# Power.net
KiCad netlist of a schematic drawn in Altium Designer
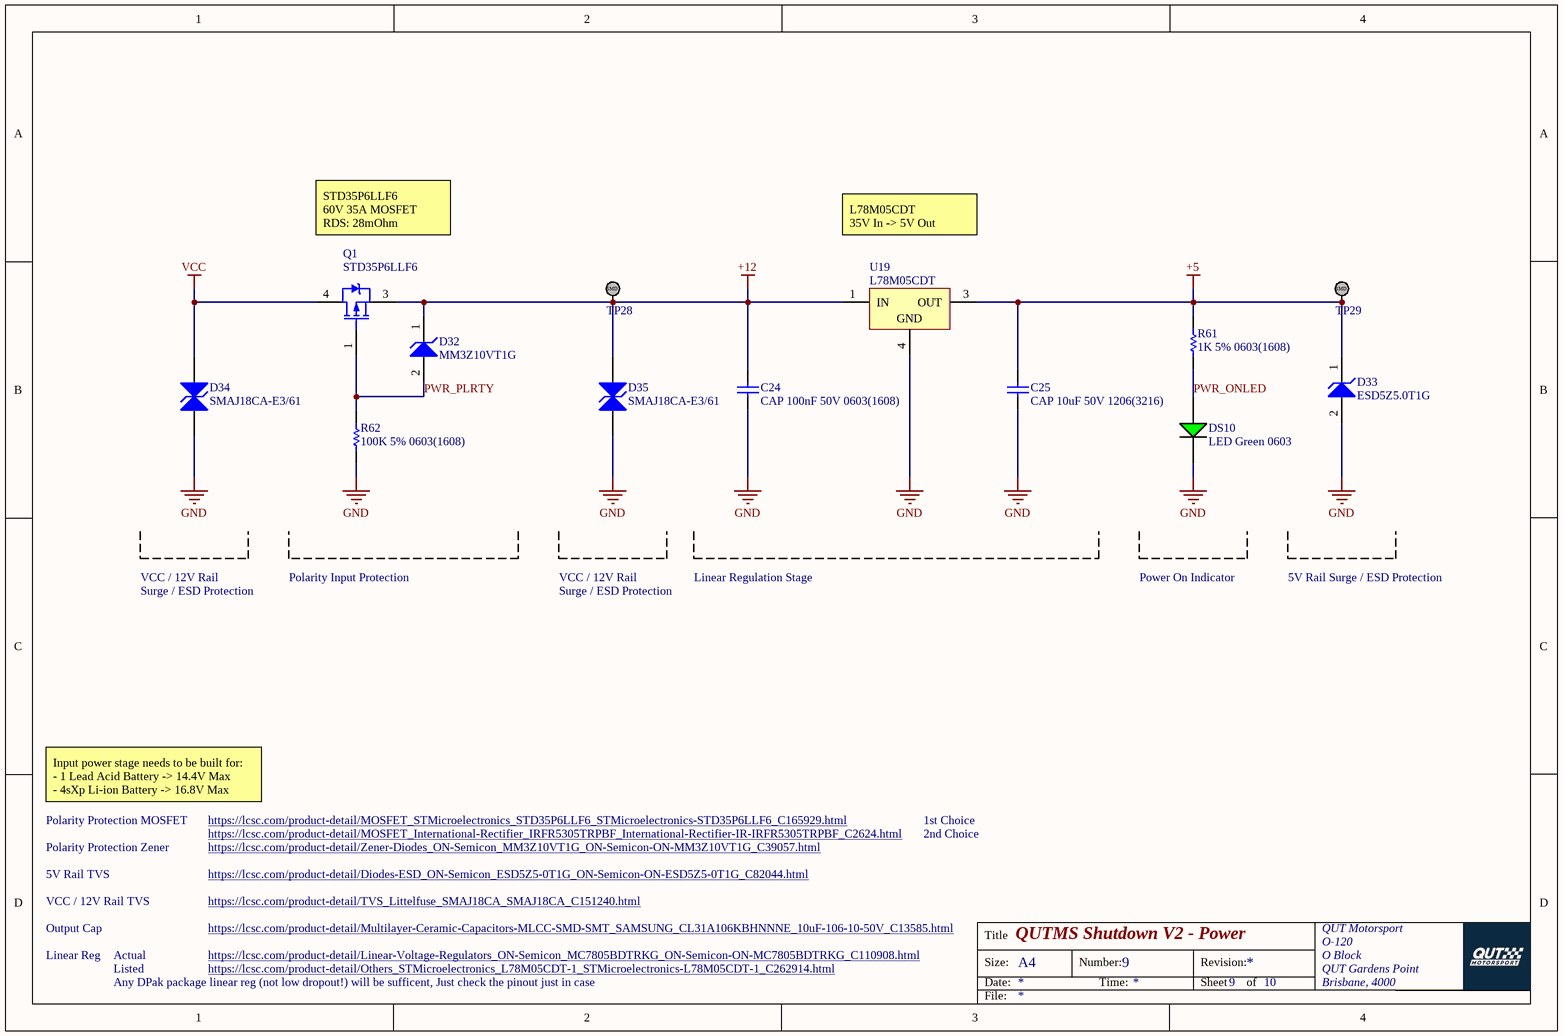
[diagram p0: Power.SchDoc]

(export (version "E")
  (design (tool "Eeschema 10.0.6"))
  (components
    (comp (ref "C24")
      (value "CAP 100nF 50V 0603(1608)")
      (footprint "CAPC0603(1608)100_N")
      (description "CAP 100nF 50V ±5% 0603 (1608 Metric) Thickness 1mm SMD")
      (fields (field (name "TOLERANCE") "Â±5%"))
      (libsource (lib "Altium Content Vault") (part "CAP"))
    )
    (comp (ref "C25")
      (value "CAP 10uF 50V 1206(3216)")
      (footprint "CAPC1206(3216)190_N")
      (description "CAP 10uF 50V ±10% 1206 (3216 Metric) Thickness 1.9mm SMD")
      (fields (field (name "TOLERANCE") "Â±10%"))
      (libsource (lib "Altium Content Vault") (part "CAP"))
    )
    (comp (ref "D32")
      (value "MM3Z10VT1G")
      (footprint "ONSC-SOD-323-2-477-02_V")
      (description "Zener Voltage Regulator, 300 mW, 2-Pin SOD-323, Pb-Free, Tape and Reel")
      (fields (field (name "MANUFACTURER") "On Semiconductor"))
      (libsource (lib "Altium Content Vault") (part "ONSC-K1A2-2"))
    )
    (comp (ref "D33")
      (value "ESD5Z5.0T1G")
      (footprint "ONSC-SOD-523-2-502-01_V")
      (fields (field (name "MANUFACTURER") "On Semiconductor"))
      (libsource (lib "Altium Content Vault") (part "ONSC-K1A2-2"))
    )
    (comp (ref "D34")
      (value "SMAJ18CA-E3/61")
      (footprint "VISH-DO-214AC-2_N")
      (fields (field (name "MANUFACTURER") "Vishay Semiconductor"))
      (libsource (lib "Altium Content Vault") (part "VISH-A1A2-2"))
    )
    (comp (ref "D35")
      (value "SMAJ18CA-E3/61")
      (footprint "VISH-DO-214AC-2_N")
      (fields (field (name "MANUFACTURER") "Vishay Semiconductor"))
      (libsource (lib "Altium Content Vault") (part "VISH-A1A2-2"))
    )
    (comp (ref "DS10")
      (value "LED Green 0603")
      (footprint "LED GREEN 0603")
      (libsource (lib "QUTMS_LEDLibrary") (part "LED GREEN 0603"))
    )
    (comp (ref "Q1")
      (value "STD35P6LLF6")
      (footprint "ONSC-DPAK-3-369C-01_V")
      (description "Power MOSFET, -60 V, -12 A, P-Channel, 3-Pin DPAK, Pb-Free, Tape and Reel")
      (fields (field (name "MANUFACTURER") "On Semiconductor") (field (name "PARTNUMBER") "NTD2955T4G"))
      (libsource (lib "Altium Content Vault") (part "ONSC-PMOS-G1S3D4-3_B"))
    )
    (comp (ref "R61")
      (value "1K 5% 0603(1608)")
      (footprint "RESC0603(1608)_N")
      (description "1K 0.1W 5% 0603 (1608 Metric)  SMD")
      (fields (field (name "TOLERANCE") "5 %") (field (name "POWER") "0.1 W"))
      (libsource (lib "Altium Content Vault") (part "RES"))
    )
    (comp (ref "R62")
      (value "100K 5% 0603(1608)")
      (footprint "RESC0603(1608)_N")
      (description "100K 0.1W 5% 0603 (1608 Metric)  SMD")
      (fields (field (name "TOLERANCE") "5 %") (field (name "POWER") "0.1 W"))
      (libsource (lib "Altium Content Vault") (part "RES"))
    )
    (comp (ref "TP28")
      (value "TestPoint_SMD")
      (footprint "TestPointSMD")
      (libsource (lib "StandardTest") (part "TestPoint_SMD"))
    )
    (comp (ref "TP29")
      (value "TestPoint_SMD")
      (footprint "TestPointSMD")
      (libsource (lib "StandardTest") (part "TestPoint_SMD"))
    )
    (comp (ref "U19")
      (value "L78M05CDT")
      (footprint "STM-TO252-3_A_V")
      (description "Precision Regulator, 0.5 A, 5 V Output, 0 to 150 degC, 3-Pin DPAK (TO252), RoHS, Tube")
      (fields (field (name "MANUFACTURER") "STMicroelectronics"))
      (libsource (lib "Altium Content Vault") (part "STM-L78M05-TO252-3"))
    )
  )
  (nets
    (net (code "1") (name "+5") (class "Default")
      (node (ref "C25") (pin "2") (pinfunction "2_2") (pintype "passive"))
      (node (ref "D33") (pin "1") (pinfunction "K_1") (pintype "passive"))
      (node (ref "R61") (pin "2") (pinfunction "2_2") (pintype "passive"))
      (node (ref "TP29") (pin "1") (pinfunction "1_1") (pintype "passive"))
      (node (ref "U19") (pin "3") (pinfunction "OUT_3") (pintype "power_in"))
    )
    (net (code "2") (name "+12") (class "Default")
      (node (ref "C24") (pin "2") (pinfunction "2_2") (pintype "passive"))
      (node (ref "D32") (pin "1") (pinfunction "K_1") (pintype "passive"))
      (node (ref "D35") (pin "2") (pinfunction "A2_2") (pintype "passive"))
      (node (ref "Q1") (pin "3") (pinfunction "S_3") (pintype "passive"))
      (node (ref "TP28") (pin "1") (pinfunction "1_1") (pintype "passive"))
      (node (ref "U19") (pin "1") (pinfunction "IN_1") (pintype "power_in"))
    )
    (net (code "3") (name "/PWR_ONLED") (class "Default")
      (node (ref "DS10") (pin "1") (pinfunction "A_1") (pintype "passive"))
      (node (ref "R61") (pin "1") (pinfunction "1_1") (pintype "passive"))
    )
    (net (code "4") (name "/PWR_PLRTY") (class "Default")
      (node (ref "D32") (pin "2") (pinfunction "A_2") (pintype "passive"))
      (node (ref "Q1") (pin "1") (pinfunction "G_1") (pintype "passive"))
      (node (ref "R62") (pin "2") (pinfunction "2_2") (pintype "passive"))
    )
    (net (code "5") (name "GND") (class "Default")
      (node (ref "C24") (pin "1") (pinfunction "1_1") (pintype "passive"))
      (node (ref "C25") (pin "1") (pinfunction "1_1") (pintype "passive"))
      (node (ref "D33") (pin "2") (pinfunction "A_2") (pintype "passive"))
      (node (ref "D34") (pin "1") (pinfunction "A1_1") (pintype "passive"))
      (node (ref "D35") (pin "1") (pinfunction "A1_1") (pintype "passive"))
      (node (ref "DS10") (pin "2") (pinfunction "C_2") (pintype "passive"))
      (node (ref "R62") (pin "1") (pinfunction "1_1") (pintype "passive"))
      (node (ref "U19") (pin "4") (pinfunction "GND_4") (pintype "power_in"))
    )
    (net (code "6") (name "VCC") (class "Default")
      (node (ref "D34") (pin "2") (pinfunction "A2_2") (pintype "passive"))
      (node (ref "Q1") (pin "4") (pinfunction "D_4") (pintype "passive"))
    )
  )
)
